# FloppyController1A.net
KiCad netlist of a schematic drawn in EAGLE
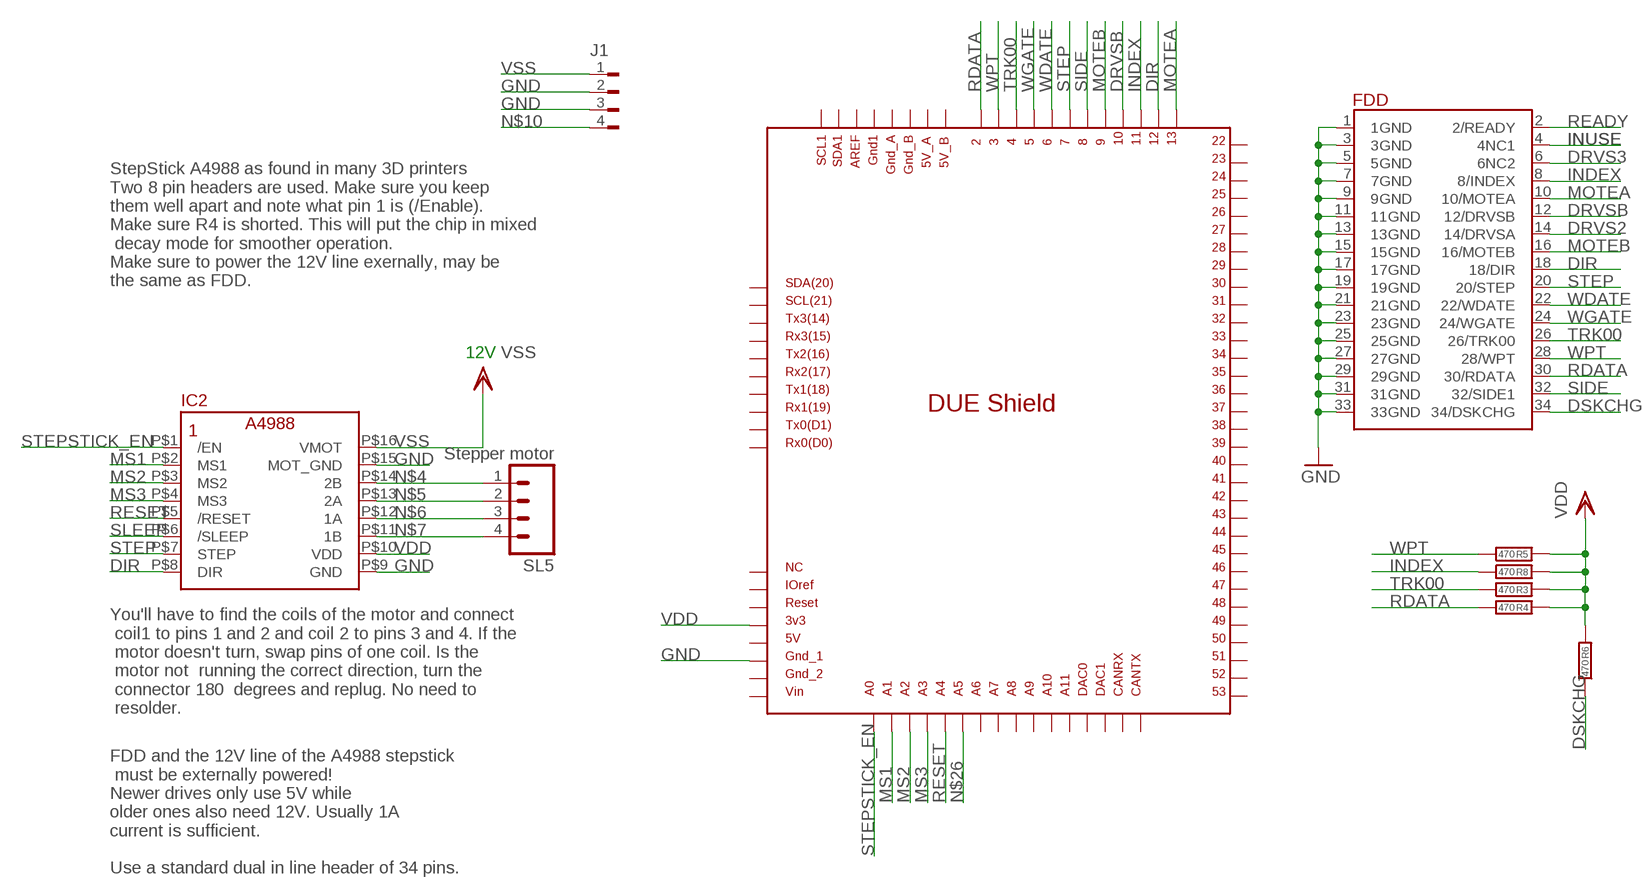
[diagram p0: schematic, sheet 1]

(export (version "E")
  (design (tool "Eeschema 10.0.6"))
  (components
    (comp (ref "FDD")
      (value "FLOPPY_34PIN_CONN")
      (footprint "eagle-import:FLOPPY_34PIN_DUALROW")
      (libsource (lib "eagle-import") (part "FLOPPY_34PIN_CONN"))
    )
    (comp (ref "IC2")
      (value "STEPSTICK_A4988")
      (footprint "eagle-import:STEPSTICK_A4988")
      (libsource (lib "eagle-import") (part "STEPSTICK_A4988"))
    )
    (comp (ref "J1")
      (value "FLOP-4W827001")
      (footprint "eagle-import:827001")
      (libsource (lib "eagle-import") (part "FLOP-4W827001"))
    )
    (comp (ref "R3")
      (value "470")
      (footprint "eagle-import:M1206")
      (libsource (lib "eagle-import") (part "R-EU_M1206"))
    )
    (comp (ref "R4")
      (value "470")
      (footprint "eagle-import:M1206")
      (libsource (lib "eagle-import") (part "R-EU_M1206"))
    )
    (comp (ref "R5")
      (value "470")
      (footprint "eagle-import:M1206")
      (libsource (lib "eagle-import") (part "R-EU_M1206"))
    )
    (comp (ref "R6")
      (value "470")
      (footprint "eagle-import:M1206")
      (libsource (lib "eagle-import") (part "R-EU_M1206"))
    )
    (comp (ref "R8")
      (value "470")
      (footprint "eagle-import:M1206")
      (libsource (lib "eagle-import") (part "R-EU_M1206"))
    )
    (comp (ref "SL5")
      (value "Stepper motor")
      (footprint "eagle-import:04P")
      (libsource (lib "eagle-import") (part "M04"))
    )
    (comp (ref "U$1")
      (value "DUE(NOCONN)")
      (footprint "eagle-import:DUE(NORMAL_NO_CONN)")
      (libsource (lib "eagle-import") (part "DUE(NOCONN)"))
    )
  )
  (nets
    (net (code "1") (name "/DIR") (class "Default")
      (node (ref "FDD") (pin "18") (pinfunction "18/DIR_18") (pintype "input"))
      (node (ref "IC2") (pin "P$8") (pinfunction "DIR_P$8") (pintype "input"))
      (node (ref "U$1") (pin "12") (pinfunction "12_12") (pintype "bidirectional"))
    )
    (net (code "2") (name "/DRVS2") (class "Default")
      (node (ref "FDD") (pin "14") (pinfunction "14/DRVSA_14") (pintype "input"))
    )
    (net (code "3") (name "/DRVS3") (class "Default")
      (node (ref "FDD") (pin "6") (pinfunction "6NC2_6") (pintype "bidirectional"))
    )
    (net (code "4") (name "/DRVSB") (class "Default")
      (node (ref "FDD") (pin "12") (pinfunction "12/DRVSB_12") (pintype "input"))
      (node (ref "U$1") (pin "10") (pinfunction "10_10") (pintype "bidirectional"))
    )
    (net (code "5") (name "/DSKCHG") (class "Default")
      (node (ref "FDD") (pin "34") (pinfunction "34/DSKCHG_34") (pintype "output"))
      (node (ref "R6") (pin "1") (pinfunction "1_1") (pintype "passive"))
    )
    (net (code "6") (name "/INDEX") (class "Default")
      (node (ref "FDD") (pin "8") (pinfunction "8/INDEX_8") (pintype "output"))
      (node (ref "R8") (pin "1") (pinfunction "1_1") (pintype "passive"))
      (node (ref "U$1") (pin "11") (pinfunction "11_11") (pintype "bidirectional"))
    )
    (net (code "7") (name "/INUSE") (class "Default")
      (node (ref "FDD") (pin "4") (pinfunction "4NC1_4") (pintype "bidirectional"))
    )
    (net (code "8") (name "/MOTEA") (class "Default")
      (node (ref "FDD") (pin "10") (pinfunction "10/MOTEA_10") (pintype "input"))
      (node (ref "U$1") (pin "13") (pinfunction "13_13") (pintype "bidirectional"))
    )
    (net (code "9") (name "/MOTEB") (class "Default")
      (node (ref "FDD") (pin "16") (pinfunction "16/MOTEB_16") (pintype "input"))
      (node (ref "U$1") (pin "9") (pinfunction "9_9") (pintype "bidirectional"))
    )
    (net (code "10") (name "/MS1") (class "Default")
      (node (ref "IC2") (pin "P$2") (pinfunction "MS1_P$2") (pintype "input"))
      (node (ref "U$1") (pin "A1") (pinfunction "A1_A1") (pintype "bidirectional"))
    )
    (net (code "11") (name "/MS2") (class "Default")
      (node (ref "IC2") (pin "P$3") (pinfunction "MS2_P$3") (pintype "input"))
      (node (ref "U$1") (pin "A2") (pinfunction "A2_A2") (pintype "bidirectional"))
    )
    (net (code "12") (name "/MS3") (class "Default")
      (node (ref "IC2") (pin "P$4") (pinfunction "MS3_P$4") (pintype "input"))
      (node (ref "U$1") (pin "A3") (pinfunction "A3_A3") (pintype "bidirectional"))
    )
    (net (code "13") (name "/N$4") (class "Default")
      (node (ref "IC2") (pin "P$14") (pinfunction "2B_P$14") (pintype "output"))
      (node (ref "SL5") (pin "1") (pinfunction "1_1") (pintype "passive"))
    )
    (net (code "14") (name "/N$5") (class "Default")
      (node (ref "IC2") (pin "P$13") (pinfunction "2A_P$13") (pintype "output"))
      (node (ref "SL5") (pin "2") (pinfunction "2_2") (pintype "passive"))
    )
    (net (code "15") (name "/N$6") (class "Default")
      (node (ref "IC2") (pin "P$12") (pinfunction "1A_P$12") (pintype "output"))
      (node (ref "SL5") (pin "3") (pinfunction "3_3") (pintype "passive"))
    )
    (net (code "16") (name "/N$7") (class "Default")
      (node (ref "IC2") (pin "P$11") (pinfunction "1B_P$11") (pintype "output"))
      (node (ref "SL5") (pin "4") (pinfunction "4_4") (pintype "passive"))
    )
    (net (code "17") (name "/N$10") (class "Default")
      (node (ref "J1") (pin "4") (pinfunction "4_4") (pintype "passive"))
    )
    (net (code "18") (name "/N$26") (class "Default")
      (node (ref "U$1") (pin "A5") (pinfunction "A5_A5") (pintype "bidirectional"))
    )
    (net (code "19") (name "/RDATA") (class "Default")
      (node (ref "FDD") (pin "30") (pinfunction "30/RDATA_30") (pintype "output"))
      (node (ref "R4") (pin "1") (pinfunction "1_1") (pintype "passive"))
      (node (ref "U$1") (pin "2") (pinfunction "2_2") (pintype "bidirectional"))
    )
    (net (code "20") (name "/READY") (class "Default")
      (node (ref "FDD") (pin "2") (pinfunction "2/READY_2") (pintype "output"))
    )
    (net (code "21") (name "/RESET") (class "Default")
      (node (ref "IC2") (pin "P$5") (pinfunction "/RESET_P$5") (pintype "input"))
      (node (ref "U$1") (pin "A4") (pinfunction "A4_A4") (pintype "bidirectional"))
    )
    (net (code "22") (name "/SIDE") (class "Default")
      (node (ref "FDD") (pin "32") (pinfunction "32/SIDE1_32") (pintype "input"))
      (node (ref "U$1") (pin "8") (pinfunction "8_8") (pintype "bidirectional"))
    )
    (net (code "23") (name "/SLEEP") (class "Default")
      (node (ref "IC2") (pin "P$6") (pinfunction "/SLEEP_P$6") (pintype "input"))
    )
    (net (code "24") (name "/STEP") (class "Default")
      (node (ref "FDD") (pin "20") (pinfunction "20/STEP_20") (pintype "input"))
      (node (ref "IC2") (pin "P$7") (pinfunction "STEP_P$7") (pintype "input"))
      (node (ref "U$1") (pin "7") (pinfunction "7_7") (pintype "bidirectional"))
    )
    (net (code "25") (name "/STEPSTICK_EN") (class "Default")
      (node (ref "IC2") (pin "P$1") (pinfunction "/EN_P$1") (pintype "input"))
      (node (ref "U$1") (pin "A0") (pinfunction "A0_A0") (pintype "bidirectional"))
    )
    (net (code "26") (name "/TRK00") (class "Default")
      (node (ref "FDD") (pin "26") (pinfunction "26/TRK00_26") (pintype "output"))
      (node (ref "R3") (pin "1") (pinfunction "1_1") (pintype "passive"))
      (node (ref "U$1") (pin "4") (pinfunction "4_4") (pintype "bidirectional"))
    )
    (net (code "27") (name "/WDATE") (class "Default")
      (node (ref "FDD") (pin "22") (pinfunction "22/WDATE_22") (pintype "input"))
      (node (ref "U$1") (pin "6") (pinfunction "6_6") (pintype "bidirectional"))
    )
    (net (code "28") (name "/WGATE") (class "Default")
      (node (ref "FDD") (pin "24") (pinfunction "24/WGATE_24") (pintype "input"))
      (node (ref "U$1") (pin "5") (pinfunction "5_5") (pintype "bidirectional"))
    )
    (net (code "29") (name "/WPT") (class "Default")
      (node (ref "FDD") (pin "28") (pinfunction "28/WPT_28") (pintype "output"))
      (node (ref "R5") (pin "1") (pinfunction "1_1") (pintype "passive"))
      (node (ref "U$1") (pin "3") (pinfunction "3_3") (pintype "bidirectional"))
    )
    (net (code "30") (name "GND") (class "Default")
      (node (ref "FDD") (pin "1") (pinfunction "1GND_1") (pintype "power_in"))
      (node (ref "FDD") (pin "11") (pinfunction "11GND_11") (pintype "power_in"))
      (node (ref "FDD") (pin "13") (pinfunction "13GND_13") (pintype "power_in"))
      (node (ref "FDD") (pin "15") (pinfunction "15GND_15") (pintype "power_in"))
      (node (ref "FDD") (pin "17") (pinfunction "17GND_17") (pintype "power_in"))
      (node (ref "FDD") (pin "19") (pinfunction "19GND_19") (pintype "power_in"))
      (node (ref "FDD") (pin "21") (pinfunction "21GND_21") (pintype "power_in"))
      (node (ref "FDD") (pin "23") (pinfunction "23GND_23") (pintype "power_in"))
      (node (ref "FDD") (pin "25") (pinfunction "25GND_25") (pintype "power_in"))
      (node (ref "FDD") (pin "27") (pinfunction "27GND_27") (pintype "power_in"))
      (node (ref "FDD") (pin "29") (pinfunction "29GND_29") (pintype "power_in"))
      (node (ref "FDD") (pin "3") (pinfunction "3GND_3") (pintype "power_in"))
      (node (ref "FDD") (pin "31") (pinfunction "31GND_31") (pintype "power_in"))
      (node (ref "FDD") (pin "33") (pinfunction "33GND_33") (pintype "power_in"))
      (node (ref "FDD") (pin "5") (pinfunction "5GND_5") (pintype "power_in"))
      (node (ref "FDD") (pin "7") (pinfunction "7GND_7") (pintype "power_in"))
      (node (ref "FDD") (pin "9") (pinfunction "9GND_9") (pintype "power_in"))
      (node (ref "IC2") (pin "P$15") (pinfunction "MOT_GND_P$15") (pintype "power_in"))
      (node (ref "IC2") (pin "P$9") (pinfunction "GND_P$9") (pintype "power_in"))
      (node (ref "J1") (pin "2") (pinfunction "2_2") (pintype "passive"))
      (node (ref "J1") (pin "3") (pinfunction "3_3") (pintype "passive"))
      (node (ref "U$1") (pin "GND_1") (pinfunction "GND_1_GND_1") (pintype "bidirectional"))
    )
    (net (code "31") (name "VDD") (class "Default")
      (node (ref "IC2") (pin "P$10") (pinfunction "VDD_P$10") (pintype "power_in"))
      (node (ref "R3") (pin "2") (pinfunction "2_2") (pintype "passive"))
      (node (ref "R4") (pin "2") (pinfunction "2_2") (pintype "passive"))
      (node (ref "R5") (pin "2") (pinfunction "2_2") (pintype "passive"))
      (node (ref "R6") (pin "2") (pinfunction "2_2") (pintype "passive"))
      (node (ref "R8") (pin "2") (pinfunction "2_2") (pintype "passive"))
      (node (ref "U$1") (pin "3V3") (pinfunction "3V3_3V3") (pintype "bidirectional"))
    )
    (net (code "32") (name "VSS") (class "Default")
      (node (ref "IC2") (pin "P$16") (pinfunction "VMOT_P$16") (pintype "power_in"))
      (node (ref "J1") (pin "1") (pinfunction "1_1") (pintype "passive"))
    )
    (net (code "33") (name "unconnected-(U$1-Pad5V)") (class "Default")
      (node (ref "U$1") (pin "5V") (pinfunction "5V_5V") (pintype "bidirectional"))
    )
    (net (code "34") (name "unconnected-(U$1-Pad5V_A)") (class "Default")
      (node (ref "U$1") (pin "5V_A") (pinfunction "5V_A_5V_A") (pintype "bidirectional"))
    )
    (net (code "35") (name "unconnected-(U$1-Pad5V_B)") (class "Default")
      (node (ref "U$1") (pin "5V_B") (pinfunction "5V_B_5V_B") (pintype "bidirectional"))
    )
    (net (code "36") (name "unconnected-(U$1-Pad22)") (class "Default")
      (node (ref "U$1") (pin "22") (pinfunction "22_22") (pintype "bidirectional"))
    )
    (net (code "37") (name "unconnected-(U$1-Pad23)") (class "Default")
      (node (ref "U$1") (pin "23") (pinfunction "23_23") (pintype "bidirectional"))
    )
    (net (code "38") (name "unconnected-(U$1-Pad24)") (class "Default")
      (node (ref "U$1") (pin "24") (pinfunction "24_24") (pintype "bidirectional"))
    )
    (net (code "39") (name "unconnected-(U$1-Pad25)") (class "Default")
      (node (ref "U$1") (pin "25") (pinfunction "25_25") (pintype "bidirectional"))
    )
    (net (code "40") (name "unconnected-(U$1-Pad26)") (class "Default")
      (node (ref "U$1") (pin "26") (pinfunction "26_26") (pintype "bidirectional"))
    )
    (net (code "41") (name "unconnected-(U$1-Pad27)") (class "Default")
      (node (ref "U$1") (pin "27") (pinfunction "27_27") (pintype "bidirectional"))
    )
    (net (code "42") (name "unconnected-(U$1-Pad28)") (class "Default")
      (node (ref "U$1") (pin "28") (pinfunction "28_28") (pintype "bidirectional"))
    )
    (net (code "43") (name "unconnected-(U$1-Pad29)") (class "Default")
      (node (ref "U$1") (pin "29") (pinfunction "29_29") (pintype "bidirectional"))
    )
    (net (code "44") (name "unconnected-(U$1-Pad30)") (class "Default")
      (node (ref "U$1") (pin "30") (pinfunction "30_30") (pintype "bidirectional"))
    )
    (net (code "45") (name "unconnected-(U$1-Pad31)") (class "Default")
      (node (ref "U$1") (pin "31") (pinfunction "31_31") (pintype "bidirectional"))
    )
    (net (code "46") (name "unconnected-(U$1-Pad32)") (class "Default")
      (node (ref "U$1") (pin "32") (pinfunction "32_32") (pintype "bidirectional"))
    )
    (net (code "47") (name "unconnected-(U$1-Pad33)") (class "Default")
      (node (ref "U$1") (pin "33") (pinfunction "33_33") (pintype "bidirectional"))
    )
    (net (code "48") (name "unconnected-(U$1-Pad34)") (class "Default")
      (node (ref "U$1") (pin "34") (pinfunction "34_34") (pintype "bidirectional"))
    )
    (net (code "49") (name "unconnected-(U$1-Pad35)") (class "Default")
      (node (ref "U$1") (pin "35") (pinfunction "35_35") (pintype "bidirectional"))
    )
    (net (code "50") (name "unconnected-(U$1-Pad36)") (class "Default")
      (node (ref "U$1") (pin "36") (pinfunction "36_36") (pintype "bidirectional"))
    )
    (net (code "51") (name "unconnected-(U$1-Pad37)") (class "Default")
      (node (ref "U$1") (pin "37") (pinfunction "37_37") (pintype "bidirectional"))
    )
    (net (code "52") (name "unconnected-(U$1-Pad38)") (class "Default")
      (node (ref "U$1") (pin "38") (pinfunction "38_38") (pintype "bidirectional"))
    )
    (net (code "53") (name "unconnected-(U$1-Pad39)") (class "Default")
      (node (ref "U$1") (pin "39") (pinfunction "39_39") (pintype "bidirectional"))
    )
    (net (code "54") (name "unconnected-(U$1-Pad40)") (class "Default")
      (node (ref "U$1") (pin "40") (pinfunction "40_40") (pintype "bidirectional"))
    )
    (net (code "55") (name "unconnected-(U$1-Pad41)") (class "Default")
      (node (ref "U$1") (pin "41") (pinfunction "41_41") (pintype "bidirectional"))
    )
    (net (code "56") (name "unconnected-(U$1-Pad42)") (class "Default")
      (node (ref "U$1") (pin "42") (pinfunction "42_42") (pintype "bidirectional"))
    )
    (net (code "57") (name "unconnected-(U$1-Pad43)") (class "Default")
      (node (ref "U$1") (pin "43") (pinfunction "43_43") (pintype "bidirectional"))
    )
    (net (code "58") (name "unconnected-(U$1-Pad44)") (class "Default")
      (node (ref "U$1") (pin "44") (pinfunction "44_44") (pintype "bidirectional"))
    )
    (net (code "59") (name "unconnected-(U$1-Pad45)") (class "Default")
      (node (ref "U$1") (pin "45") (pinfunction "45_45") (pintype "bidirectional"))
    )
    (net (code "60") (name "unconnected-(U$1-Pad46)") (class "Default")
      (node (ref "U$1") (pin "46") (pinfunction "46_46") (pintype "bidirectional"))
    )
    (net (code "61") (name "unconnected-(U$1-Pad47)") (class "Default")
      (node (ref "U$1") (pin "47") (pinfunction "47_47") (pintype "bidirectional"))
    )
    (net (code "62") (name "unconnected-(U$1-Pad48)") (class "Default")
      (node (ref "U$1") (pin "48") (pinfunction "48_48") (pintype "bidirectional"))
    )
    (net (code "63") (name "unconnected-(U$1-Pad49)") (class "Default")
      (node (ref "U$1") (pin "49") (pinfunction "49_49") (pintype "bidirectional"))
    )
    (net (code "64") (name "unconnected-(U$1-Pad50)") (class "Default")
      (node (ref "U$1") (pin "50") (pinfunction "50_50") (pintype "bidirectional"))
    )
    (net (code "65") (name "unconnected-(U$1-Pad51)") (class "Default")
      (node (ref "U$1") (pin "51") (pinfunction "51_51") (pintype "bidirectional"))
    )
    (net (code "66") (name "unconnected-(U$1-Pad52)") (class "Default")
      (node (ref "U$1") (pin "52") (pinfunction "52_52") (pintype "bidirectional"))
    )
    (net (code "67") (name "unconnected-(U$1-Pad53)") (class "Default")
      (node (ref "U$1") (pin "53") (pinfunction "53_53") (pintype "bidirectional"))
    )
    (net (code "68") (name "unconnected-(U$1-PadA6)") (class "Default")
      (node (ref "U$1") (pin "A6") (pinfunction "A6_A6") (pintype "bidirectional"))
    )
    (net (code "69") (name "unconnected-(U$1-PadA7)") (class "Default")
      (node (ref "U$1") (pin "A7") (pinfunction "A7_A7") (pintype "bidirectional"))
    )
    (net (code "70") (name "unconnected-(U$1-PadA8)") (class "Default")
      (node (ref "U$1") (pin "A8") (pinfunction "A8_A8") (pintype "bidirectional"))
    )
    (net (code "71") (name "unconnected-(U$1-PadA9)") (class "Default")
      (node (ref "U$1") (pin "A9") (pinfunction "A9_A9") (pintype "bidirectional"))
    )
    (net (code "72") (name "unconnected-(U$1-PadA10)") (class "Default")
      (node (ref "U$1") (pin "A10") (pinfunction "A10_A10") (pintype "bidirectional"))
    )
    (net (code "73") (name "unconnected-(U$1-PadA11)") (class "Default")
      (node (ref "U$1") (pin "A11") (pinfunction "A11_A11") (pintype "bidirectional"))
    )
    (net (code "74") (name "unconnected-(U$1-PadAREF)") (class "Default")
      (node (ref "U$1") (pin "AREF") (pinfunction "AREF_AREF") (pintype "bidirectional"))
    )
    (net (code "75") (name "unconnected-(U$1-PadCANRX)") (class "Default")
      (node (ref "U$1") (pin "CANRX") (pinfunction "CANRX_CANRX") (pintype "bidirectional"))
    )
    (net (code "76") (name "unconnected-(U$1-PadCANTX)") (class "Default")
      (node (ref "U$1") (pin "CANTX") (pinfunction "CANTX_CANTX") (pintype "bidirectional"))
    )
    (net (code "77") (name "unconnected-(U$1-PadDAC0)") (class "Default")
      (node (ref "U$1") (pin "DAC0") (pinfunction "DAC0_DAC0") (pintype "bidirectional"))
    )
    (net (code "78") (name "unconnected-(U$1-PadDAC1)") (class "Default")
      (node (ref "U$1") (pin "DAC1") (pinfunction "DAC1_DAC1") (pintype "bidirectional"))
    )
    (net (code "79") (name "unconnected-(U$1-PadGND1)") (class "Default")
      (node (ref "U$1") (pin "GND1") (pinfunction "GND1_GND1") (pintype "bidirectional"))
    )
    (net (code "80") (name "unconnected-(U$1-PadGND_2)") (class "Default")
      (node (ref "U$1") (pin "GND_2") (pinfunction "GND_2_GND_2") (pintype "bidirectional"))
    )
    (net (code "81") (name "unconnected-(U$1-PadGND_A)") (class "Default")
      (node (ref "U$1") (pin "GND_A") (pinfunction "GND_A_GND_A") (pintype "bidirectional"))
    )
    (net (code "82") (name "unconnected-(U$1-PadGND_B)") (class "Default")
      (node (ref "U$1") (pin "GND_B") (pinfunction "GND_B_GND_B") (pintype "bidirectional"))
    )
    (net (code "83") (name "unconnected-(U$1-PadIOREF)") (class "Default")
      (node (ref "U$1") (pin "IOREF") (pinfunction "IOREF_IOREF") (pintype "bidirectional"))
    )
    (net (code "84") (name "unconnected-(U$1-PadNC)") (class "Default")
      (node (ref "U$1") (pin "NC") (pinfunction "NC_NC") (pintype "bidirectional"))
    )
    (net (code "85") (name "unconnected-(U$1-PadRESET)") (class "Default")
      (node (ref "U$1") (pin "RESET") (pinfunction "RESET_RESET") (pintype "bidirectional"))
    )
    (net (code "86") (name "unconnected-(U$1-PadRX0)") (class "Default")
      (node (ref "U$1") (pin "RX0") (pinfunction "RX0_RX0") (pintype "bidirectional"))
    )
    (net (code "87") (name "unconnected-(U$1-PadRX1)") (class "Default")
      (node (ref "U$1") (pin "RX1") (pinfunction "RX1_RX1") (pintype "bidirectional"))
    )
    (net (code "88") (name "unconnected-(U$1-PadRX2)") (class "Default")
      (node (ref "U$1") (pin "RX2") (pinfunction "RX2_RX2") (pintype "bidirectional"))
    )
    (net (code "89") (name "unconnected-(U$1-PadRX3)") (class "Default")
      (node (ref "U$1") (pin "RX3") (pinfunction "RX3_RX3") (pintype "bidirectional"))
    )
    (net (code "90") (name "unconnected-(U$1-PadSCL)") (class "Default")
      (node (ref "U$1") (pin "SCL") (pinfunction "SCL_SCL") (pintype "bidirectional"))
    )
    (net (code "91") (name "unconnected-(U$1-PadSCL1)") (class "Default")
      (node (ref "U$1") (pin "SCL1") (pinfunction "SCL1_SCL1") (pintype "bidirectional"))
    )
    (net (code "92") (name "unconnected-(U$1-PadSDA)") (class "Default")
      (node (ref "U$1") (pin "SDA") (pinfunction "SDA_SDA") (pintype "bidirectional"))
    )
    (net (code "93") (name "unconnected-(U$1-PadSDA1)") (class "Default")
      (node (ref "U$1") (pin "SDA1") (pinfunction "SDA1_SDA1") (pintype "bidirectional"))
    )
    (net (code "94") (name "unconnected-(U$1-PadTX0)") (class "Default")
      (node (ref "U$1") (pin "TX0") (pinfunction "TX0_TX0") (pintype "bidirectional"))
    )
    (net (code "95") (name "unconnected-(U$1-PadTX1)") (class "Default")
      (node (ref "U$1") (pin "TX1") (pinfunction "TX1_TX1") (pintype "bidirectional"))
    )
    (net (code "96") (name "unconnected-(U$1-PadTX2)") (class "Default")
      (node (ref "U$1") (pin "TX2") (pinfunction "TX2_TX2") (pintype "bidirectional"))
    )
    (net (code "97") (name "unconnected-(U$1-PadTX3)") (class "Default")
      (node (ref "U$1") (pin "TX3") (pinfunction "TX3_TX3") (pintype "bidirectional"))
    )
    (net (code "98") (name "unconnected-(U$1-PadVIN)") (class "Default")
      (node (ref "U$1") (pin "VIN") (pinfunction "VIN_VIN") (pintype "bidirectional"))
    )
  )
)
